# 02_USB2UART.net
KiCad netlist of a schematic drawn in Altium Designer
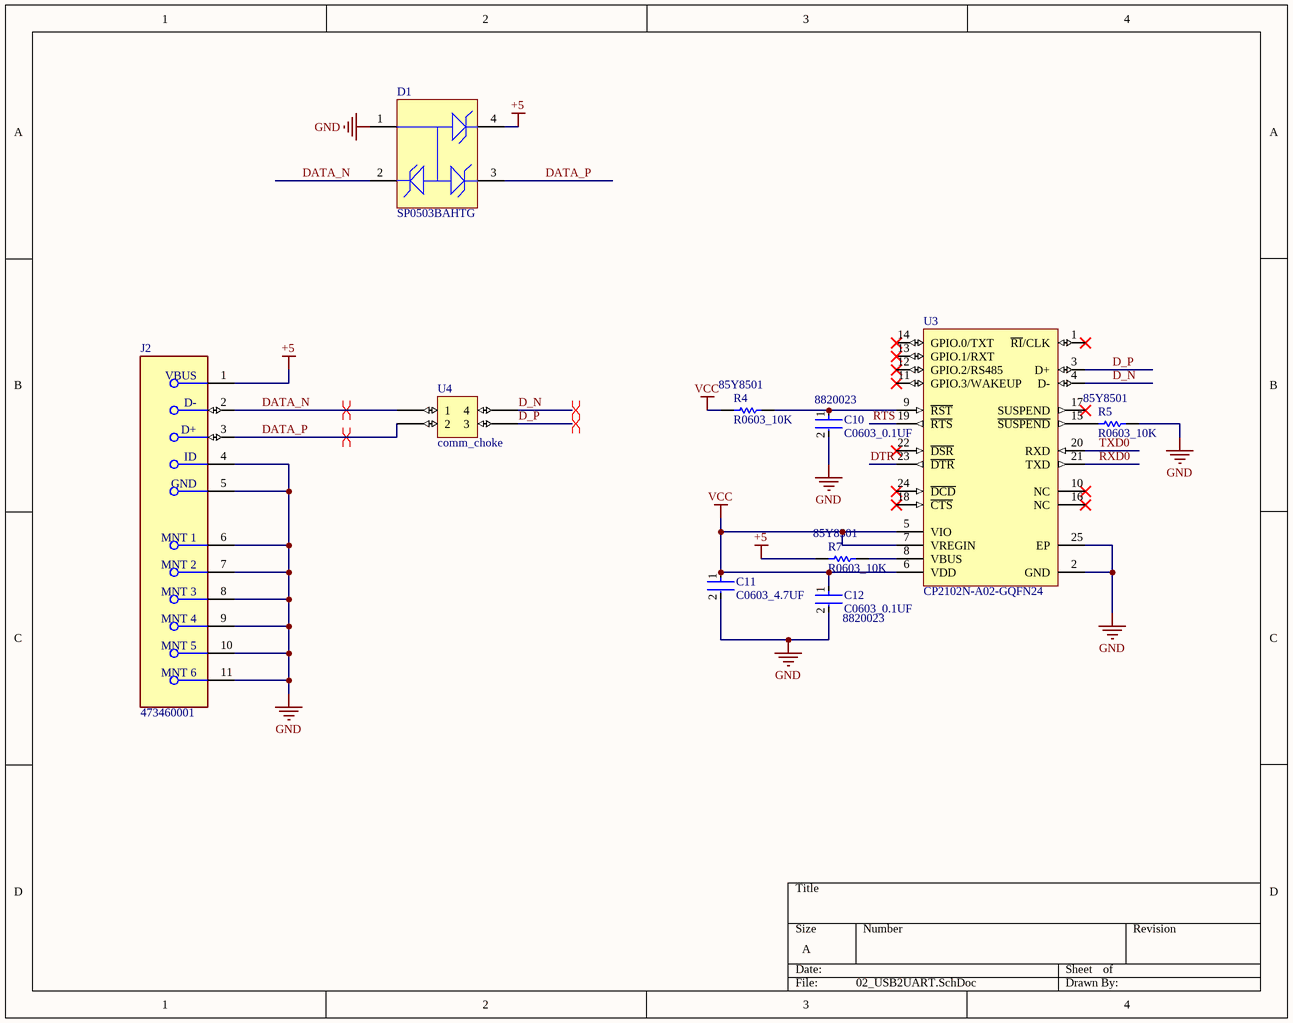
[diagram p0: 02_USB2UART.SchDoc]

(export (version "E")
  (design (tool "Eeschema 10.0.6"))
  (components
    (comp (ref "C10")
      (value "C0603_0.1UF")
      (footprint "FP-C0603C-CF-IPC_B")
      (description "Multilayer Ceramic Capacitors MLCC Surface Mount 0603 0.1uF 50 Volts X7R 10%")
      (fields
        (field (name "SUPPLIER PART NUMBER 1") "8820023")
        (field (name "MANUFACTURER") "Murata")
        (field (name "MANUFACTURER PART NUMBER") "GRM188R71H104KA93D")
      )
      (libsource (lib "RBS_library") (part "C0603"))
    )
    (comp (ref "C11")
      (value "C0603_4.7UF")
      (footprint "FP-C0603C-CF-IPC_B")
      (description "CAP CER 4.7UF 0603")
      (fields
        (field (name "MANUFACTURER") "Murata")
        (field (name "MANUFACTURER PART NUMBER") "GRM155R60J475ME47D")
      )
      (libsource (lib "RBS_library") (part "C0603"))
    )
    (comp (ref "C12")
      (value "C0603_0.1UF")
      (footprint "FP-C0603C-CF-IPC_B")
      (description "Multilayer Ceramic Capacitors MLCC Surface Mount 0603 0.1uF 50 Volts X7R 10%")
      (fields
        (field (name "SUPPLIER PART NUMBER 1") "8820023")
        (field (name "MANUFACTURER") "Murata")
        (field (name "MANUFACTURER PART NUMBER") "GRM188R71H104KA93D")
      )
      (libsource (lib "RBS_library") (part "C0603"))
    )
    (comp (ref "D1")
      (value "SP0503BAHTG")
      (footprint "LFUS-SOT143-4_V")
      (description "TVS Diode Array, 30 pF, 30 KV, -40 to 85 degC, 4-Pin SOT143, RoHS, Tape and Reel")
      (fields (field (name "MANUFACTURER") "Littelfuse"))
      (libsource (lib "Altium Content Vault") (part "LFUS-SP0503BAHTG-SOT143-4"))
    )
    (comp (ref "J2")
      (value "473460001")
      (footprint "FP-473460001-MFG")
      (description "CONN RCPT USB2.0 MICRO B SMD R/A")
      (fields
        (field (name "OCTOPART") "https://octopart.com/47346-0001-molex-7164928")
        (field (name "MANUFACTURER") "Molex")
      )
      (libsource (lib "Altium Content Vault") (part "53ae1f1d9b557310b43ca686e5bb76a"))
    )
    (comp (ref "R4")
      (value "R0603_10K")
      (footprint "RESC1609X55X30LL15T15")
      (description "PANASONIC - ERJ-3EKF1002V. - THICK FILM CHIP RES, 0603, 1%, PRECISION")
      (fields
        (field (name "SUPPLIER PART NUMBER 1") "85Y8501")
        (field (name "MANUFACTURER") "Panasonic")
        (field (name "MANUFACTURER PART NUMBER") "ERJ-3EKF1002V")
      )
      (libsource (lib "RBS_library") (part "R0603"))
    )
    (comp (ref "R5")
      (value "R0603_10K")
      (footprint "RESC1609X55X30LL15T15")
      (description "PANASONIC - ERJ-3EKF1002V. - THICK FILM CHIP RES, 0603, 1%, PRECISION")
      (fields
        (field (name "SUPPLIER PART NUMBER 1") "85Y8501")
        (field (name "MANUFACTURER") "Panasonic")
        (field (name "MANUFACTURER PART NUMBER") "ERJ-3EKF1002V")
      )
      (libsource (lib "RBS_library") (part "R0603"))
    )
    (comp (ref "R7")
      (value "R0603_10K")
      (footprint "RESC1609X55X30LL15T15")
      (description "PANASONIC - ERJ-3EKF1002V. - THICK FILM CHIP RES, 0603, 1%, PRECISION")
      (fields
        (field (name "SUPPLIER PART NUMBER 1") "85Y8501")
        (field (name "MANUFACTURER") "Panasonic")
        (field (name "MANUFACTURER PART NUMBER") "ERJ-3EKF1002V")
      )
      (libsource (lib "RBS_library") (part "R0603"))
    )
    (comp (ref "U3")
      (value "CP2102N-A02-GQFN24")
      (footprint "SLAB-QFN-24-2550x2550TP_A_V")
      (description "USBXpress(TM) Family, 4 GPIOs, 2.2 to 3.6 V, -40 to 85 degC, 24-Pin QFN, RoHS")
      (fields (field (name "MANUFACTURER") "Silicon Labs"))
      (libsource (lib "Finger_module") (part "CMP-2000-07570-1"))
    )
    (comp (ref "U4")
      (value "comm_choke")
      (footprint "EXC14CE900U")
      (description "EXC14CE900U")
      (libsource (lib "RBS_library") (part "comm_choke"))
    )
  )
  (nets
    (net (code "1") (name "+5") (class "Default")
      (node (ref "D1") (pin "4") (pinfunction "4_4") (pintype "passive"))
      (node (ref "J2") (pin "1") (pinfunction "VBUS_1") (pintype "power_in"))
      (node (ref "R7") (pin "1") (pinfunction "1_1") (pintype "passive"))
    )
    (net (code "2") (name "/DATA_N") (class "Default")
      (node (ref "D1") (pin "2") (pinfunction "2_2") (pintype "passive"))
      (node (ref "J2") (pin "2") (pinfunction "D-_2") (pintype "bidirectional"))
      (node (ref "U4") (pin "1") (pinfunction "1_1") (pintype "bidirectional"))
    )
    (net (code "3") (name "/DATA_P") (class "Default")
      (node (ref "D1") (pin "3") (pinfunction "3_3") (pintype "passive"))
      (node (ref "J2") (pin "3") (pinfunction "D+_3") (pintype "bidirectional"))
      (node (ref "U4") (pin "2") (pinfunction "2_2") (pintype "bidirectional"))
    )
    (net (code "4") (name "/DTR") (class "Default")
      (node (ref "U3") (pin "23") (pinfunction "~{DTR}_23") (pintype "output"))
    )
    (net (code "5") (name "/D_N") (class "Default")
      (node (ref "U3") (pin "4") (pinfunction "D-_4") (pintype "bidirectional"))
      (node (ref "U4") (pin "4") (pinfunction "4_4") (pintype "bidirectional"))
    )
    (net (code "6") (name "/D_P") (class "Default")
      (node (ref "U3") (pin "3") (pinfunction "D+_3") (pintype "bidirectional"))
      (node (ref "U4") (pin "3") (pinfunction "3_3") (pintype "bidirectional"))
    )
    (net (code "7") (name "/RTS") (class "Default")
      (node (ref "U3") (pin "19") (pinfunction "~{RTS}_19") (pintype "output"))
    )
    (net (code "8") (name "/RXD0") (class "Default")
      (node (ref "U3") (pin "21") (pinfunction "TXD_21") (pintype "output"))
    )
    (net (code "9") (name "/TXD0") (class "Default")
      (node (ref "U3") (pin "20") (pinfunction "RXD_20") (pintype "input"))
    )
    (net (code "10") (name "GND") (class "Default")
      (node (ref "C10") (pin "2") (pinfunction "2_2") (pintype "passive"))
      (node (ref "C11") (pin "2") (pinfunction "2_2") (pintype "passive"))
      (node (ref "C12") (pin "2") (pinfunction "2_2") (pintype "passive"))
      (node (ref "D1") (pin "1") (pinfunction "1_1") (pintype "passive"))
      (node (ref "J2") (pin "10") (pinfunction "MNT_5_10") (pintype "passive"))
      (node (ref "J2") (pin "11") (pinfunction "MNT_6_11") (pintype "passive"))
      (node (ref "J2") (pin "4") (pinfunction "ID_4") (pintype "passive"))
      (node (ref "J2") (pin "5") (pinfunction "GND_5") (pintype "power_in"))
      (node (ref "J2") (pin "6") (pinfunction "MNT_1_6") (pintype "passive"))
      (node (ref "J2") (pin "7") (pinfunction "MNT_2_7") (pintype "passive"))
      (node (ref "J2") (pin "8") (pinfunction "MNT_3_8") (pintype "passive"))
      (node (ref "J2") (pin "9") (pinfunction "MNT_4_9") (pintype "passive"))
      (node (ref "R5") (pin "2") (pinfunction "2_2") (pintype "passive"))
      (node (ref "U3") (pin "2") (pinfunction "GND_2") (pintype "power_in"))
      (node (ref "U3") (pin "25") (pinfunction "EP_25") (pintype "power_in"))
    )
    (net (code "11") (name "Net-(U3-VBUS)") (class "Default")
      (node (ref "R7") (pin "2") (pinfunction "2_2") (pintype "passive"))
      (node (ref "U3") (pin "8") (pinfunction "VBUS_8") (pintype "power_in"))
    )
    (net (code "12") (name "Net-(U3-~{RST})") (class "Default")
      (node (ref "C10") (pin "1") (pinfunction "1_1") (pintype "passive"))
      (node (ref "R4") (pin "2") (pinfunction "2_2") (pintype "passive"))
      (node (ref "U3") (pin "9") (pinfunction "~{RST}_9") (pintype "input"))
    )
    (net (code "13") (name "Net-(U3-~{SUSPEND})") (class "Default")
      (node (ref "R5") (pin "1") (pinfunction "1_1") (pintype "passive"))
      (node (ref "U3") (pin "15") (pinfunction "~{SUSPEND}_15") (pintype "output"))
    )
    (net (code "14") (name "VCC") (class "Default")
      (node (ref "C11") (pin "1") (pinfunction "1_1") (pintype "passive"))
      (node (ref "C12") (pin "1") (pinfunction "1_1") (pintype "passive"))
      (node (ref "R4") (pin "1") (pinfunction "1_1") (pintype "passive"))
      (node (ref "U3") (pin "5") (pinfunction "VIO_5") (pintype "power_in"))
      (node (ref "U3") (pin "6") (pinfunction "VDD_6") (pintype "power_in"))
      (node (ref "U3") (pin "7") (pinfunction "VREGIN_7") (pintype "power_in"))
    )
    (net (code "15") (name "unconnected-(U3-GPIO.0{slash}TXT-Pad14)") (class "Default")
      (node (ref "U3") (pin "14") (pinfunction "GPIO.0/TXT_14") (pintype "bidirectional+no_connect"))
    )
    (net (code "16") (name "unconnected-(U3-GPIO.1{slash}RXT-Pad13)") (class "Default")
      (node (ref "U3") (pin "13") (pinfunction "GPIO.1/RXT_13") (pintype "bidirectional+no_connect"))
    )
    (net (code "17") (name "unconnected-(U3-GPIO.2{slash}RS485-Pad12)") (class "Default")
      (node (ref "U3") (pin "12") (pinfunction "GPIO.2/RS485_12") (pintype "bidirectional+no_connect"))
    )
    (net (code "18") (name "unconnected-(U3-GPIO.3{slash}WAKEUP-Pad11)") (class "Default")
      (node (ref "U3") (pin "11") (pinfunction "GPIO.3/WAKEUP_11") (pintype "bidirectional+no_connect"))
    )
    (net (code "19") (name "unconnected-(U3-NC-Pad10)") (class "Default")
      (node (ref "U3") (pin "10") (pinfunction "NC_10") (pintype "passive+no_connect"))
    )
    (net (code "20") (name "unconnected-(U3-NC-Pad16)") (class "Default")
      (node (ref "U3") (pin "16") (pinfunction "NC_16") (pintype "passive+no_connect"))
    )
    (net (code "21") (name "unconnected-(U3-SUSPEND-Pad17)") (class "Default")
      (node (ref "U3") (pin "17") (pinfunction "SUSPEND_17") (pintype "output+no_connect"))
    )
    (net (code "22") (name "unconnected-(U3-~{CTS}-Pad18)") (class "Default")
      (node (ref "U3") (pin "18") (pinfunction "~{CTS}_18") (pintype "input+no_connect"))
    )
    (net (code "23") (name "unconnected-(U3-~{DCD}-Pad24)") (class "Default")
      (node (ref "U3") (pin "24") (pinfunction "~{DCD}_24") (pintype "input+no_connect"))
    )
    (net (code "24") (name "unconnected-(U3-~{DSR}-Pad22)") (class "Default")
      (node (ref "U3") (pin "22") (pinfunction "~{DSR}_22") (pintype "input+no_connect"))
    )
    (net (code "25") (name "unconnected-(U3-~{RI}{slash}CLK-Pad1)") (class "Default")
      (node (ref "U3") (pin "1") (pinfunction "~{RI}/CLK_1") (pintype "bidirectional+no_connect"))
    )
  )
)
